# atmega1284p-dip2.net
KiCad netlist of a schematic drawn in EAGLE
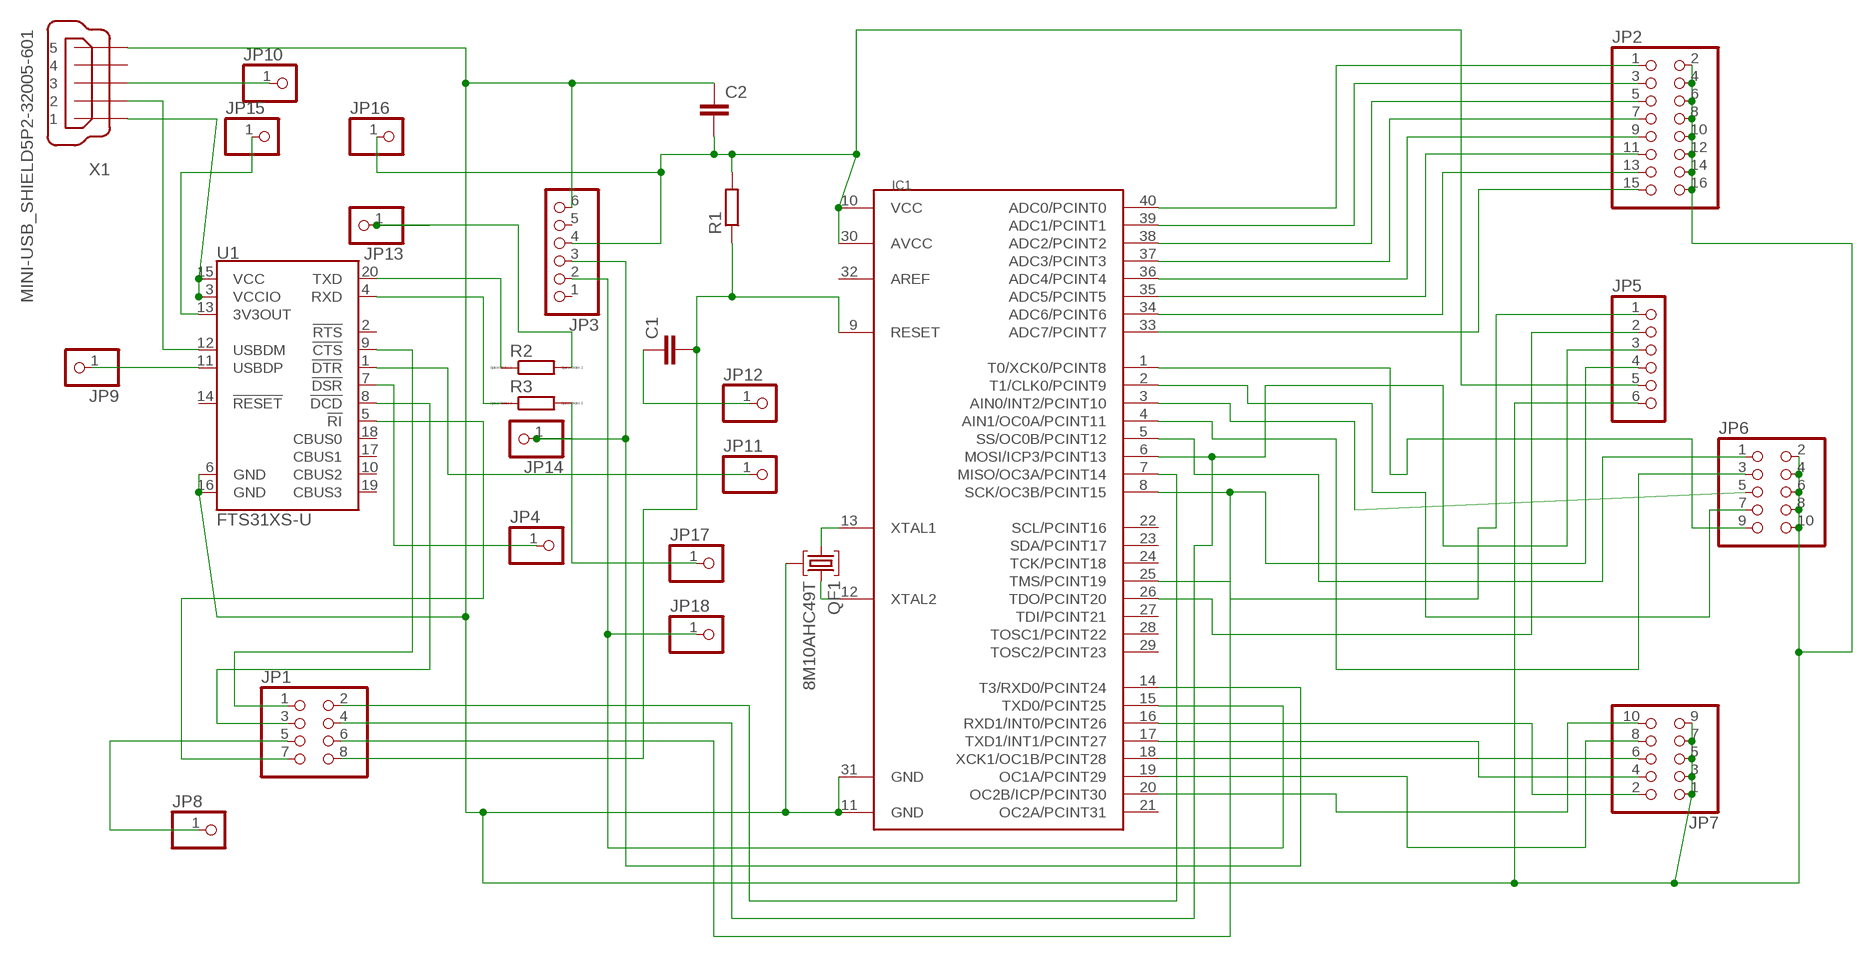
[diagram p0: schematic, sheet 1]

(export (version "E")
  (design (tool "Eeschema 10.0.6"))
  (components
    (comp (ref "C1")
      (value "C-EUC0805")
      (footprint "eagle-import:C0805")
      (libsource (lib "eagle-import") (part "C-EUC0805"))
    )
    (comp (ref "C2")
      (value "C-EUC0805")
      (footprint "eagle-import:C0805")
      (libsource (lib "eagle-import") (part "C-EUC0805"))
    )
    (comp (ref "IC1")
      (value "MEGA1284P")
      (footprint "eagle-import:DIL40")
      (libsource (lib "eagle-import") (part "MEGA1284P"))
    )
    (comp (ref "JP1")
      (value "PINHD-2X4")
      (footprint "eagle-import:2X04")
      (libsource (lib "eagle-import") (part "PINHD-2X4"))
    )
    (comp (ref "JP2")
      (value "PINHD-2X8")
      (footprint "eagle-import:2X08")
      (libsource (lib "eagle-import") (part "PINHD-2X8"))
    )
    (comp (ref "JP3")
      (value "PINHD-1X6")
      (footprint "eagle-import:1X06")
      (libsource (lib "eagle-import") (part "PINHD-1X6"))
    )
    (comp (ref "JP4")
      (value "PINHD-1X1")
      (footprint "eagle-import:1X01")
      (libsource (lib "eagle-import") (part "PINHD-1X1"))
    )
    (comp (ref "JP5")
      (value "PINHD-1X6")
      (footprint "eagle-import:1X06")
      (libsource (lib "eagle-import") (part "PINHD-1X6"))
    )
    (comp (ref "JP6")
      (value "PINHD-2X5")
      (footprint "eagle-import:2X05")
      (libsource (lib "eagle-import") (part "PINHD-2X5"))
    )
    (comp (ref "JP7")
      (value "PINHD-2X5")
      (footprint "eagle-import:2X05")
      (libsource (lib "eagle-import") (part "PINHD-2X5"))
    )
    (comp (ref "JP8")
      (value "PINHD-1X1")
      (footprint "eagle-import:1X01")
      (libsource (lib "eagle-import") (part "PINHD-1X1"))
    )
    (comp (ref "JP9")
      (value "PINHD-1X1")
      (footprint "eagle-import:1X01")
      (libsource (lib "eagle-import") (part "PINHD-1X1"))
    )
    (comp (ref "JP10")
      (value "PINHD-1X1")
      (footprint "eagle-import:1X01")
      (libsource (lib "eagle-import") (part "PINHD-1X1"))
    )
    (comp (ref "JP11")
      (value "PINHD-1X1")
      (footprint "eagle-import:1X01")
      (libsource (lib "eagle-import") (part "PINHD-1X1"))
    )
    (comp (ref "JP12")
      (value "PINHD-1X1")
      (footprint "eagle-import:1X01")
      (libsource (lib "eagle-import") (part "PINHD-1X1"))
    )
    (comp (ref "JP13")
      (value "PINHD-1X1")
      (footprint "eagle-import:1X01")
      (libsource (lib "eagle-import") (part "PINHD-1X1"))
    )
    (comp (ref "JP14")
      (value "PINHD-1X1")
      (footprint "eagle-import:1X01")
      (libsource (lib "eagle-import") (part "PINHD-1X1"))
    )
    (comp (ref "JP15")
      (value "PINHD-1X1")
      (footprint "eagle-import:1X01")
      (libsource (lib "eagle-import") (part "PINHD-1X1"))
    )
    (comp (ref "JP16")
      (value "PINHD-1X1")
      (footprint "eagle-import:1X01")
      (libsource (lib "eagle-import") (part "PINHD-1X1"))
    )
    (comp (ref "JP17")
      (value "PINHD-1X1")
      (footprint "eagle-import:1X01")
      (libsource (lib "eagle-import") (part "PINHD-1X1"))
    )
    (comp (ref "JP18")
      (value "PINHD-1X1")
      (footprint "eagle-import:1X01")
      (libsource (lib "eagle-import") (part "PINHD-1X1"))
    )
    (comp (ref "QF1")
      (value "8M10AHC49T")
      (footprint "eagle-import:HC49U")
      (libsource (lib "eagle-import") (part "8M10AHC49T"))
    )
    (comp (ref "R1")
      (value "R-EU_R0805")
      (footprint "eagle-import:R0805")
      (libsource (lib "eagle-import") (part "R-EU_R0805"))
    )
    (comp (ref "R2")
      (value "RR0603")
      (footprint "eagle-import:R0603")
      (libsource (lib "eagle-import") (part "RR0603"))
    )
    (comp (ref "R3")
      (value "RR0603")
      (footprint "eagle-import:R0603")
      (libsource (lib "eagle-import") (part "RR0603"))
    )
    (comp (ref "U1")
      (value "FTS31XS-U")
      (footprint "eagle-import:SSOP20_L")
      (libsource (lib "eagle-import") (part "FT231XS"))
    )
    (comp (ref "X1")
      (value "MINI-USB_SHIELD5P2-32005-601")
      (footprint "eagle-import:32005-601")
      (libsource (lib "eagle-import") (part "MINI-USB_SHIELD5P2-32005-601"))
    )
  )
  (nets
    (net (code "1") (name "Net-(C1-Pad1)") (class "Default")
      (node (ref "C1") (pin "1") (pinfunction "1_1") (pintype "passive"))
      (node (ref "JP12") (pin "1") (pinfunction "1_1") (pintype "passive"))
    )
    (net (code "2") (name "Net-(C2-Pad1)") (class "Default")
      (node (ref "C2") (pin "1") (pinfunction "1_1") (pintype "passive"))
      (node (ref "IC1") (pin "11") (pinfunction "GND_11") (pintype "bidirectional"))
      (node (ref "IC1") (pin "31") (pinfunction "GND_31") (pintype "bidirectional"))
      (node (ref "JP2") (pin "10") (pinfunction "10_10") (pintype "passive"))
      (node (ref "JP2") (pin "12") (pinfunction "12_12") (pintype "passive"))
      (node (ref "JP2") (pin "14") (pinfunction "14_14") (pintype "passive"))
      (node (ref "JP2") (pin "16") (pinfunction "16_16") (pintype "passive"))
      (node (ref "JP2") (pin "2") (pinfunction "2_2") (pintype "passive"))
      (node (ref "JP2") (pin "4") (pinfunction "4_4") (pintype "passive"))
      (node (ref "JP2") (pin "6") (pinfunction "6_6") (pintype "passive"))
      (node (ref "JP2") (pin "8") (pinfunction "8_8") (pintype "passive"))
      (node (ref "JP3") (pin "6") (pinfunction "6_6") (pintype "passive"))
      (node (ref "JP5") (pin "6") (pinfunction "6_6") (pintype "passive"))
      (node (ref "JP6") (pin "10") (pinfunction "10_10") (pintype "passive"))
      (node (ref "JP6") (pin "2") (pinfunction "2_2") (pintype "passive"))
      (node (ref "JP6") (pin "4") (pinfunction "4_4") (pintype "passive"))
      (node (ref "JP6") (pin "6") (pinfunction "6_6") (pintype "passive"))
      (node (ref "JP6") (pin "8") (pinfunction "8_8") (pintype "passive"))
      (node (ref "JP7") (pin "1") (pinfunction "1_1") (pintype "passive"))
      (node (ref "JP7") (pin "3") (pinfunction "3_3") (pintype "passive"))
      (node (ref "JP7") (pin "5") (pinfunction "5_5") (pintype "passive"))
      (node (ref "JP7") (pin "7") (pinfunction "7_7") (pintype "passive"))
      (node (ref "JP7") (pin "9") (pinfunction "9_9") (pintype "passive"))
      (node (ref "QF1") (pin "2") (pinfunction "2_2") (pintype "passive"))
      (node (ref "U1") (pin "16") (pinfunction "GND_16") (pintype "bidirectional"))
      (node (ref "U1") (pin "6") (pinfunction "GND_6") (pintype "bidirectional"))
      (node (ref "X1") (pin "5") (pinfunction "5_5") (pintype "passive"))
    )
    (net (code "3") (name "Net-(IC1-ADC0{slash}PCINT0)") (class "Default")
      (node (ref "IC1") (pin "40") (pinfunction "ADC0/PCINT0_40") (pintype "bidirectional"))
      (node (ref "JP2") (pin "1") (pinfunction "1_1") (pintype "passive"))
    )
    (net (code "4") (name "Net-(IC1-ADC1{slash}PCINT1)") (class "Default")
      (node (ref "IC1") (pin "39") (pinfunction "ADC1/PCINT1_39") (pintype "bidirectional"))
      (node (ref "JP2") (pin "3") (pinfunction "3_3") (pintype "passive"))
    )
    (net (code "5") (name "Net-(IC1-ADC2{slash}PCINT2)") (class "Default")
      (node (ref "IC1") (pin "38") (pinfunction "ADC2/PCINT2_38") (pintype "bidirectional"))
      (node (ref "JP2") (pin "5") (pinfunction "5_5") (pintype "passive"))
    )
    (net (code "6") (name "Net-(IC1-ADC3{slash}PCINT3)") (class "Default")
      (node (ref "IC1") (pin "37") (pinfunction "ADC3/PCINT3_37") (pintype "bidirectional"))
      (node (ref "JP2") (pin "7") (pinfunction "7_7") (pintype "passive"))
    )
    (net (code "7") (name "Net-(IC1-ADC4{slash}PCINT4)") (class "Default")
      (node (ref "IC1") (pin "36") (pinfunction "ADC4/PCINT4_36") (pintype "bidirectional"))
      (node (ref "JP2") (pin "9") (pinfunction "9_9") (pintype "passive"))
    )
    (net (code "8") (name "Net-(IC1-ADC5{slash}PCINT5)") (class "Default")
      (node (ref "IC1") (pin "35") (pinfunction "ADC5/PCINT5_35") (pintype "bidirectional"))
      (node (ref "JP2") (pin "11") (pinfunction "11_11") (pintype "passive"))
    )
    (net (code "9") (name "Net-(IC1-ADC6{slash}PCINT6)") (class "Default")
      (node (ref "IC1") (pin "34") (pinfunction "ADC6/PCINT6_34") (pintype "bidirectional"))
      (node (ref "JP2") (pin "13") (pinfunction "13_13") (pintype "passive"))
    )
    (net (code "10") (name "Net-(IC1-ADC7{slash}PCINT7)") (class "Default")
      (node (ref "IC1") (pin "33") (pinfunction "ADC7/PCINT7_33") (pintype "bidirectional"))
      (node (ref "JP2") (pin "15") (pinfunction "15_15") (pintype "passive"))
    )
    (net (code "11") (name "Net-(IC1-AIN0{slash}INT2{slash}PCINT10)") (class "Default")
      (node (ref "IC1") (pin "3") (pinfunction "AIN0/INT2/PCINT10_3") (pintype "bidirectional"))
      (node (ref "JP6") (pin "5") (pinfunction "5_5") (pintype "passive"))
    )
    (net (code "12") (name "Net-(IC1-AIN1{slash}OC0A{slash}PCINT11)") (class "Default")
      (node (ref "IC1") (pin "4") (pinfunction "AIN1/OC0A/PCINT11_4") (pintype "bidirectional"))
      (node (ref "JP6") (pin "3") (pinfunction "3_3") (pintype "passive"))
    )
    (net (code "13") (name "Net-(IC1-AVCC)") (class "Default")
      (node (ref "C2") (pin "2") (pinfunction "2_2") (pintype "passive"))
      (node (ref "IC1") (pin "10") (pinfunction "VCC_10") (pintype "bidirectional"))
      (node (ref "IC1") (pin "30") (pinfunction "AVCC_30") (pintype "bidirectional"))
      (node (ref "JP16") (pin "1") (pinfunction "1_1") (pintype "passive"))
      (node (ref "JP3") (pin "4") (pinfunction "4_4") (pintype "passive"))
      (node (ref "JP5") (pin "5") (pinfunction "5_5") (pintype "passive"))
      (node (ref "R1") (pin "2") (pinfunction "2_2") (pintype "passive"))
    )
    (net (code "14") (name "Net-(IC1-MISO{slash}OC3A{slash}PCINT14)") (class "Default")
      (node (ref "IC1") (pin "7") (pinfunction "MISO/OC3A/PCINT14_7") (pintype "bidirectional"))
      (node (ref "JP1") (pin "2") (pinfunction "2_2") (pintype "passive"))
    )
    (net (code "15") (name "Net-(IC1-MOSI{slash}ICP3{slash}PCINT13)") (class "Default")
      (node (ref "IC1") (pin "6") (pinfunction "MOSI/ICP3/PCINT13_6") (pintype "bidirectional"))
      (node (ref "JP1") (pin "4") (pinfunction "4_4") (pintype "passive"))
      (node (ref "JP5") (pin "3") (pinfunction "3_3") (pintype "passive"))
    )
    (net (code "16") (name "Net-(IC1-OC1A{slash}PCINT29)") (class "Default")
      (node (ref "IC1") (pin "19") (pinfunction "OC1A/PCINT29_19") (pintype "bidirectional"))
      (node (ref "JP7") (pin "8") (pinfunction "8_8") (pintype "passive"))
    )
    (net (code "17") (name "Net-(IC1-OC2B{slash}ICP{slash}PCINT30)") (class "Default")
      (node (ref "IC1") (pin "20") (pinfunction "OC2B/ICP/PCINT30_20") (pintype "bidirectional"))
      (node (ref "JP7") (pin "10") (pinfunction "10_10") (pintype "passive"))
    )
    (net (code "18") (name "Net-(IC1-RESET)") (class "Default")
      (node (ref "C1") (pin "2") (pinfunction "2_2") (pintype "passive"))
      (node (ref "IC1") (pin "9") (pinfunction "RESET_9") (pintype "bidirectional"))
      (node (ref "JP1") (pin "8") (pinfunction "8_8") (pintype "passive"))
      (node (ref "R1") (pin "1") (pinfunction "1_1") (pintype "passive"))
    )
    (net (code "19") (name "Net-(IC1-RXD1{slash}INT0{slash}PCINT26)") (class "Default")
      (node (ref "IC1") (pin "16") (pinfunction "RXD1/INT0/PCINT26_16") (pintype "bidirectional"))
      (node (ref "JP7") (pin "2") (pinfunction "2_2") (pintype "passive"))
    )
    (net (code "20") (name "Net-(IC1-SCK{slash}OC3B{slash}PCINT15)") (class "Default")
      (node (ref "IC1") (pin "8") (pinfunction "SCK/OC3B/PCINT15_8") (pintype "bidirectional"))
      (node (ref "JP1") (pin "6") (pinfunction "6_6") (pintype "passive"))
      (node (ref "JP5") (pin "4") (pinfunction "4_4") (pintype "passive"))
    )
    (net (code "21") (name "Net-(IC1-SS{slash}OC0B{slash}PCINT12)") (class "Default")
      (node (ref "IC1") (pin "5") (pinfunction "SS/OC0B/PCINT12_5") (pintype "bidirectional"))
      (node (ref "JP6") (pin "1") (pinfunction "1_1") (pintype "passive"))
    )
    (net (code "22") (name "Net-(IC1-T0{slash}XCK0{slash}PCINT8)") (class "Default")
      (node (ref "IC1") (pin "1") (pinfunction "T0/XCK0/PCINT8_1") (pintype "bidirectional"))
      (node (ref "JP6") (pin "9") (pinfunction "9_9") (pintype "passive"))
    )
    (net (code "23") (name "Net-(IC1-T1{slash}CLK0{slash}PCINT9)") (class "Default")
      (node (ref "IC1") (pin "2") (pinfunction "T1/CLK0/PCINT9_2") (pintype "bidirectional"))
      (node (ref "JP6") (pin "7") (pinfunction "7_7") (pintype "passive"))
    )
    (net (code "24") (name "Net-(IC1-T3{slash}RXD0{slash}PCINT24)") (class "Default")
      (node (ref "IC1") (pin "14") (pinfunction "T3/RXD0/PCINT24_14") (pintype "bidirectional"))
      (node (ref "JP14") (pin "1") (pinfunction "1_1") (pintype "passive"))
      (node (ref "JP3") (pin "3") (pinfunction "3_3") (pintype "passive"))
    )
    (net (code "25") (name "Net-(IC1-TDO{slash}PCINT20)") (class "Default")
      (node (ref "IC1") (pin "26") (pinfunction "TDO/PCINT20_26") (pintype "bidirectional"))
      (node (ref "JP5") (pin "2") (pinfunction "2_2") (pintype "passive"))
    )
    (net (code "26") (name "Net-(IC1-TMS{slash}PCINT19)") (class "Default")
      (node (ref "IC1") (pin "25") (pinfunction "TMS/PCINT19_25") (pintype "bidirectional"))
      (node (ref "JP5") (pin "1") (pinfunction "1_1") (pintype "passive"))
    )
    (net (code "27") (name "Net-(IC1-TXD0{slash}PCINT25)") (class "Default")
      (node (ref "IC1") (pin "15") (pinfunction "TXD0/PCINT25_15") (pintype "bidirectional"))
      (node (ref "JP18") (pin "1") (pinfunction "1_1") (pintype "passive"))
      (node (ref "JP3") (pin "2") (pinfunction "2_2") (pintype "passive"))
    )
    (net (code "28") (name "Net-(IC1-TXD1{slash}INT1{slash}PCINT27)") (class "Default")
      (node (ref "IC1") (pin "17") (pinfunction "TXD1/INT1/PCINT27_17") (pintype "bidirectional"))
      (node (ref "JP7") (pin "4") (pinfunction "4_4") (pintype "passive"))
    )
    (net (code "29") (name "Net-(IC1-XCK1{slash}OC1B{slash}PCINT28)") (class "Default")
      (node (ref "IC1") (pin "18") (pinfunction "XCK1/OC1B/PCINT28_18") (pintype "bidirectional"))
      (node (ref "JP7") (pin "6") (pinfunction "6_6") (pintype "passive"))
    )
    (net (code "30") (name "Net-(IC1-XTAL1)") (class "Default")
      (node (ref "IC1") (pin "13") (pinfunction "XTAL1_13") (pintype "bidirectional"))
      (node (ref "QF1") (pin "1") (pinfunction "1_1") (pintype "passive"))
    )
    (net (code "31") (name "Net-(IC1-XTAL2)") (class "Default")
      (node (ref "IC1") (pin "12") (pinfunction "XTAL2_12") (pintype "bidirectional"))
      (node (ref "QF1") (pin "3") (pinfunction "3_3") (pintype "passive"))
    )
    (net (code "32") (name "Net-(JP1-Pad5)") (class "Default")
      (node (ref "JP1") (pin "5") (pinfunction "5_5") (pintype "passive"))
      (node (ref "JP8") (pin "1") (pinfunction "1_1") (pintype "passive"))
    )
    (net (code "33") (name "Net-(JP10-Pad1)") (class "Default")
      (node (ref "JP10") (pin "1") (pinfunction "1_1") (pintype "passive"))
      (node (ref "X1") (pin "3") (pinfunction "3_3") (pintype "passive"))
    )
    (net (code "34") (name "Net-(JP13-Pad1)") (class "Default")
      (node (ref "JP13") (pin "1") (pinfunction "1_1") (pintype "passive"))
      (node (ref "R2") (pin "2") (pinfunction "2_2") (pintype "passive"))
    )
    (net (code "35") (name "Net-(JP17-Pad1)") (class "Default")
      (node (ref "JP17") (pin "1") (pinfunction "1_1") (pintype "passive"))
      (node (ref "R3") (pin "2") (pinfunction "2_2") (pintype "passive"))
    )
    (net (code "36") (name "Net-(U1-3V3OUT)") (class "Default")
      (node (ref "JP15") (pin "1") (pinfunction "1_1") (pintype "passive"))
      (node (ref "U1") (pin "13") (pinfunction "3V3OUT_13") (pintype "bidirectional"))
    )
    (net (code "37") (name "Net-(U1-RXD)") (class "Default")
      (node (ref "R3") (pin "1") (pinfunction "1_1") (pintype "passive"))
      (node (ref "U1") (pin "4") (pinfunction "RXD_4") (pintype "bidirectional"))
    )
    (net (code "38") (name "Net-(U1-TXD)") (class "Default")
      (node (ref "R2") (pin "1") (pinfunction "1_1") (pintype "passive"))
      (node (ref "U1") (pin "20") (pinfunction "TXD_20") (pintype "bidirectional"))
    )
    (net (code "39") (name "Net-(U1-USBDM)") (class "Default")
      (node (ref "U1") (pin "12") (pinfunction "USBDM_12") (pintype "bidirectional"))
      (node (ref "X1") (pin "2") (pinfunction "2_2") (pintype "passive"))
    )
    (net (code "40") (name "Net-(U1-USBDP)") (class "Default")
      (node (ref "JP9") (pin "1") (pinfunction "1_1") (pintype "passive"))
      (node (ref "U1") (pin "11") (pinfunction "USBDP_11") (pintype "bidirectional"))
    )
    (net (code "41") (name "Net-(U1-VCC)") (class "Default")
      (node (ref "U1") (pin "15") (pinfunction "VCC_15") (pintype "bidirectional"))
      (node (ref "U1") (pin "3") (pinfunction "VCCIO_3") (pintype "bidirectional"))
      (node (ref "X1") (pin "1") (pinfunction "1_1") (pintype "passive"))
    )
    (net (code "42") (name "Net-(U1-~{CTS})") (class "Default")
      (node (ref "JP1") (pin "1") (pinfunction "1_1") (pintype "passive"))
      (node (ref "U1") (pin "9") (pinfunction "~{CTS}_9") (pintype "bidirectional"))
    )
    (net (code "43") (name "Net-(U1-~{DCD})") (class "Default")
      (node (ref "JP1") (pin "3") (pinfunction "3_3") (pintype "passive"))
      (node (ref "U1") (pin "8") (pinfunction "~{DCD}_8") (pintype "bidirectional"))
    )
    (net (code "44") (name "Net-(U1-~{DSR})") (class "Default")
      (node (ref "JP4") (pin "1") (pinfunction "1_1") (pintype "passive"))
      (node (ref "U1") (pin "7") (pinfunction "~{DSR}_7") (pintype "bidirectional"))
    )
    (net (code "45") (name "Net-(U1-~{DTR})") (class "Default")
      (node (ref "JP11") (pin "1") (pinfunction "1_1") (pintype "passive"))
      (node (ref "U1") (pin "1") (pinfunction "~{DTR}_1") (pintype "bidirectional"))
    )
    (net (code "46") (name "Net-(U1-~{RI})") (class "Default")
      (node (ref "JP1") (pin "7") (pinfunction "7_7") (pintype "passive"))
      (node (ref "U1") (pin "5") (pinfunction "~{RI}_5") (pintype "bidirectional"))
    )
    (net (code "47") (name "unconnected-(IC1-AREF-Pad32)") (class "Default")
      (node (ref "IC1") (pin "32") (pinfunction "AREF_32") (pintype "bidirectional"))
    )
    (net (code "48") (name "unconnected-(IC1-OC2A{slash}PCINT31-Pad21)") (class "Default")
      (node (ref "IC1") (pin "21") (pinfunction "OC2A/PCINT31_21") (pintype "bidirectional"))
    )
    (net (code "49") (name "unconnected-(IC1-SCL{slash}PCINT16-Pad22)") (class "Default")
      (node (ref "IC1") (pin "22") (pinfunction "SCL/PCINT16_22") (pintype "bidirectional"))
    )
    (net (code "50") (name "unconnected-(IC1-SDA{slash}PCINT17-Pad23)") (class "Default")
      (node (ref "IC1") (pin "23") (pinfunction "SDA/PCINT17_23") (pintype "bidirectional"))
    )
    (net (code "51") (name "unconnected-(IC1-TCK{slash}PCINT18-Pad24)") (class "Default")
      (node (ref "IC1") (pin "24") (pinfunction "TCK/PCINT18_24") (pintype "bidirectional"))
    )
    (net (code "52") (name "unconnected-(IC1-TDI{slash}PCINT21-Pad27)") (class "Default")
      (node (ref "IC1") (pin "27") (pinfunction "TDI/PCINT21_27") (pintype "bidirectional"))
    )
    (net (code "53") (name "unconnected-(IC1-TOSC1{slash}PCINT22-Pad28)") (class "Default")
      (node (ref "IC1") (pin "28") (pinfunction "TOSC1/PCINT22_28") (pintype "bidirectional"))
    )
    (net (code "54") (name "unconnected-(IC1-TOSC2{slash}PCINT23-Pad29)") (class "Default")
      (node (ref "IC1") (pin "29") (pinfunction "TOSC2/PCINT23_29") (pintype "bidirectional"))
    )
    (net (code "55") (name "unconnected-(JP3-Pad1)") (class "Default")
      (node (ref "JP3") (pin "1") (pinfunction "1_1") (pintype "passive"))
    )
    (net (code "56") (name "unconnected-(JP3-Pad5)") (class "Default")
      (node (ref "JP3") (pin "5") (pinfunction "5_5") (pintype "passive"))
    )
    (net (code "57") (name "unconnected-(U1-CBUS0-Pad18)") (class "Default")
      (node (ref "U1") (pin "18") (pinfunction "CBUS0_18") (pintype "bidirectional"))
    )
    (net (code "58") (name "unconnected-(U1-CBUS1-Pad17)") (class "Default")
      (node (ref "U1") (pin "17") (pinfunction "CBUS1_17") (pintype "bidirectional"))
    )
    (net (code "59") (name "unconnected-(U1-CBUS2-Pad10)") (class "Default")
      (node (ref "U1") (pin "10") (pinfunction "CBUS2_10") (pintype "bidirectional"))
    )
    (net (code "60") (name "unconnected-(U1-CBUS3-Pad19)") (class "Default")
      (node (ref "U1") (pin "19") (pinfunction "CBUS3_19") (pintype "bidirectional"))
    )
    (net (code "61") (name "unconnected-(U1-~{RESET}-Pad14)") (class "Default")
      (node (ref "U1") (pin "14") (pinfunction "~{RESET}_14") (pintype "bidirectional"))
    )
    (net (code "62") (name "unconnected-(U1-~{RTS}-Pad2)") (class "Default")
      (node (ref "U1") (pin "2") (pinfunction "~{RTS}_2") (pintype "bidirectional"))
    )
    (net (code "63") (name "unconnected-(X1-Pad4)") (class "Default")
      (node (ref "X1") (pin "4") (pinfunction "4_4") (pintype "passive"))
    )
  )
)
